# Arduino_LCD_Clock_rev_1.net
KiCad netlist of a schematic drawn in EAGLE
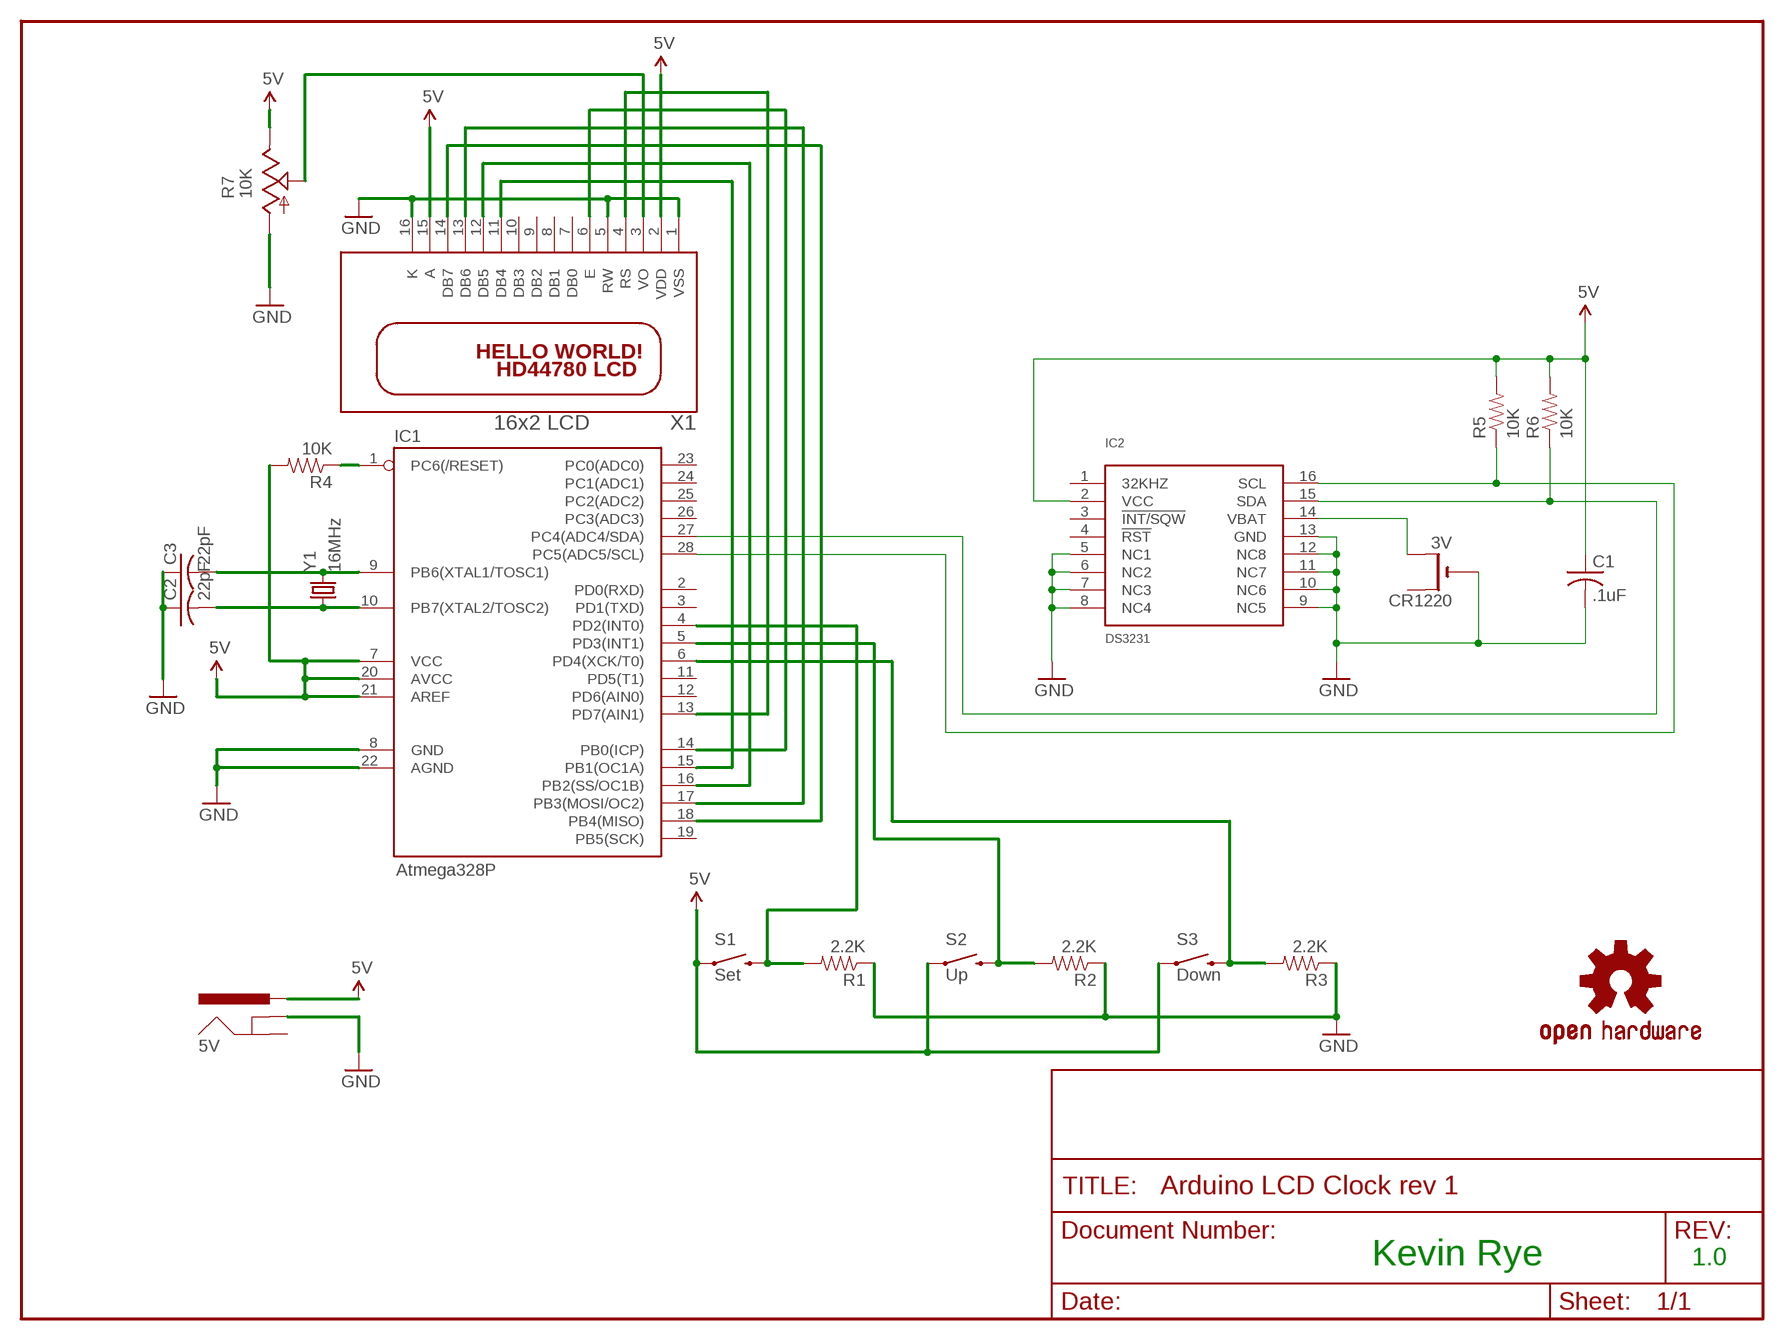
[diagram p0: schematic, sheet 1]

(export (version "E")
  (design (tool "Eeschema 10.0.6"))
  (components
    (comp (ref "5V")
      (value "POWER_JACKSLT")
      (footprint "eagle-import:POWER_JACK_SLOT")
      (libsource (lib "eagle-import") (part "POWER_JACKSLT"))
    )
    (comp (ref "C1")
      (value ".1uF")
      (footprint "eagle-import:C025-024X044")
      (libsource (lib "eagle-import") (part "C-US025-024X044"))
    )
    (comp (ref "C2")
      (value "22pF")
      (footprint "eagle-import:C025-024X044")
      (libsource (lib "eagle-import") (part "C-US025-024X044"))
    )
    (comp (ref "C3")
      (value "22pF")
      (footprint "eagle-import:C025-024X044")
      (libsource (lib "eagle-import") (part "C-US025-024X044"))
    )
    (comp (ref "CR1220")
      (value "3V")
      (footprint "eagle-import:CR1220-THM")
      (libsource (lib "eagle-import") (part "CR1220THM"))
    )
    (comp (ref "IC1")
      (value "Atmega328P")
      (footprint "eagle-import:DIL28-3")
      (libsource (lib "eagle-import") (part "AVR-MEGA8-PPTH"))
    )
    (comp (ref "IC2")
      (value "DS3231")
      (footprint "eagle-import:SO16W")
      (libsource (lib "eagle-import") (part "DS3231SN"))
    )
    (comp (ref "R1")
      (value "2.2K")
      (footprint "eagle-import:AXIAL-0.4")
      (libsource (lib "eagle-import") (part "RESISTORPTH-1/4W"))
    )
    (comp (ref "R2")
      (value "2.2K")
      (footprint "eagle-import:AXIAL-0.4")
      (libsource (lib "eagle-import") (part "RESISTORPTH-1/4W"))
    )
    (comp (ref "R3")
      (value "2.2K")
      (footprint "eagle-import:AXIAL-0.4")
      (libsource (lib "eagle-import") (part "RESISTORPTH-1/4W"))
    )
    (comp (ref "R4")
      (value "10K")
      (footprint "eagle-import:AXIAL-0.4")
      (libsource (lib "eagle-import") (part "RESISTORPTH-1/4W"))
    )
    (comp (ref "R5")
      (value "10K")
      (footprint "eagle-import:AXIAL-0.4")
      (libsource (lib "eagle-import") (part "RESISTORPTH-1/4W"))
    )
    (comp (ref "R6")
      (value "10K")
      (footprint "eagle-import:AXIAL-0.4")
      (libsource (lib "eagle-import") (part "RESISTORPTH-1/4W"))
    )
    (comp (ref "R7")
      (value "10K")
      (footprint "eagle-import:S63S")
      (libsource (lib "eagle-import") (part "TRIM_US-S63S"))
    )
    (comp (ref "S1")
      (value "Set")
      (footprint "eagle-import:TACTILE-PTH-12MM")
      (libsource (lib "eagle-import") (part "SWITCH-MOMENTARY-212MM"))
    )
    (comp (ref "S2")
      (value "Up")
      (footprint "eagle-import:TACTILE-PTH-12MM")
      (libsource (lib "eagle-import") (part "SWITCH-MOMENTARY-212MM"))
    )
    (comp (ref "S3")
      (value "Down")
      (footprint "eagle-import:TACTILE-PTH-12MM")
      (libsource (lib "eagle-import") (part "SWITCH-MOMENTARY-212MM"))
    )
    (comp (ref "U$2")
      (value "OSHW-LOGOM")
      (footprint "eagle-import:OSHW-LOGO-M")
      (libsource (lib "eagle-import") (part "OSHW-LOGOM"))
    )
    (comp (ref "X1")
      (value "16x2 LCD")
      (footprint "eagle-import:LCD1602")
      (libsource (lib "eagle-import") (part "HD44780LCD-1602"))
    )
    (comp (ref "Y1")
      (value "16MHz")
      (footprint "eagle-import:HC49US")
      (libsource (lib "eagle-import") (part "CRYSTALHC49US"))
    )
  )
  (nets
    (net (code "1") (name "5V") (class "Default")
      (node (ref "5V") (pin "PWR") (pinfunction "PWR_PWR") (pintype "bidirectional"))
      (node (ref "C1") (pin "1") (pinfunction "1_1") (pintype "passive"))
      (node (ref "IC1") (pin "20") (pinfunction "AVCC_20") (pintype "bidirectional"))
      (node (ref "IC1") (pin "21") (pinfunction "AREF_21") (pintype "bidirectional"))
      (node (ref "IC1") (pin "7") (pinfunction "VCC_7") (pintype "bidirectional"))
      (node (ref "IC2") (pin "2") (pinfunction "VCC_2") (pintype "bidirectional"))
      (node (ref "R4") (pin "P$2") (pinfunction "2_P$2") (pintype "passive"))
      (node (ref "R5") (pin "P$2") (pinfunction "2_P$2") (pintype "passive"))
      (node (ref "R6") (pin "P$2") (pinfunction "2_P$2") (pintype "passive"))
      (node (ref "R7") (pin "E") (pinfunction "E_E") (pintype "passive"))
      (node (ref "S1") (pin "1") (pinfunction "1_1") (pintype "passive"))
      (node (ref "S2") (pin "1") (pinfunction "1_1") (pintype "passive"))
      (node (ref "S3") (pin "1") (pinfunction "1_1") (pintype "passive"))
      (node (ref "X1") (pin "15") (pinfunction "A_15") (pintype "input"))
      (node (ref "X1") (pin "2") (pinfunction "VDD_2") (pintype "power_in"))
    )
    (net (code "2") (name "GND") (class "Default")
      (node (ref "5V") (pin "GND@1") (pinfunction "GNDBREAK_GND@1") (pintype "bidirectional"))
      (node (ref "C1") (pin "2") (pinfunction "2_2") (pintype "passive"))
      (node (ref "C2") (pin "1") (pinfunction "1_1") (pintype "passive"))
      (node (ref "C3") (pin "1") (pinfunction "1_1") (pintype "passive"))
      (node (ref "CR1220") (pin "-") (pinfunction "-_-") (pintype "passive"))
      (node (ref "IC1") (pin "22") (pinfunction "AGND_22") (pintype "bidirectional"))
      (node (ref "IC1") (pin "8") (pinfunction "GND_8") (pintype "bidirectional"))
      (node (ref "IC2") (pin "10") (pinfunction "NC6_10") (pintype "bidirectional"))
      (node (ref "IC2") (pin "11") (pinfunction "NC7_11") (pintype "bidirectional"))
      (node (ref "IC2") (pin "12") (pinfunction "NC8_12") (pintype "bidirectional"))
      (node (ref "IC2") (pin "13") (pinfunction "GND_13") (pintype "bidirectional"))
      (node (ref "IC2") (pin "5") (pinfunction "NC1_5") (pintype "bidirectional"))
      (node (ref "IC2") (pin "6") (pinfunction "NC2_6") (pintype "bidirectional"))
      (node (ref "IC2") (pin "7") (pinfunction "NC3_7") (pintype "bidirectional"))
      (node (ref "IC2") (pin "8") (pinfunction "NC4_8") (pintype "bidirectional"))
      (node (ref "IC2") (pin "9") (pinfunction "NC5_9") (pintype "bidirectional"))
      (node (ref "R1") (pin "P$1") (pinfunction "1_P$1") (pintype "passive"))
      (node (ref "R2") (pin "P$1") (pinfunction "1_P$1") (pintype "passive"))
      (node (ref "R3") (pin "P$1") (pinfunction "1_P$1") (pintype "passive"))
      (node (ref "R7") (pin "A") (pinfunction "A_A") (pintype "passive"))
      (node (ref "X1") (pin "1") (pinfunction "VSS_1") (pintype "power_in"))
      (node (ref "X1") (pin "16") (pinfunction "K_16") (pintype "input"))
      (node (ref "X1") (pin "5") (pinfunction "RW_5") (pintype "input"))
    )
    (net (code "3") (name "Net-(CR1220-+1)") (class "Default")
      (node (ref "CR1220") (pin "+2") (pinfunction "+1_+2") (pintype "passive"))
      (node (ref "IC2") (pin "14") (pinfunction "VBAT_14") (pintype "bidirectional"))
    )
    (net (code "4") (name "Net-(IC1-PB0(ICP))") (class "Default")
      (node (ref "IC1") (pin "14") (pinfunction "PB0(ICP)_14") (pintype "bidirectional"))
      (node (ref "X1") (pin "6") (pinfunction "E_6") (pintype "input"))
    )
    (net (code "5") (name "Net-(IC1-PB1(OC1A))") (class "Default")
      (node (ref "IC1") (pin "15") (pinfunction "PB1(OC1A)_15") (pintype "bidirectional"))
      (node (ref "X1") (pin "11") (pinfunction "DB4_11") (pintype "bidirectional"))
    )
    (net (code "6") (name "Net-(IC1-PB2(SS{slash}OC1B))") (class "Default")
      (node (ref "IC1") (pin "16") (pinfunction "PB2(SS/OC1B)_16") (pintype "bidirectional"))
      (node (ref "X1") (pin "12") (pinfunction "DB5_12") (pintype "bidirectional"))
    )
    (net (code "7") (name "Net-(IC1-PB3(MOSI{slash}OC2))") (class "Default")
      (node (ref "IC1") (pin "17") (pinfunction "PB3(MOSI/OC2)_17") (pintype "bidirectional"))
      (node (ref "X1") (pin "13") (pinfunction "DB6_13") (pintype "bidirectional"))
    )
    (net (code "8") (name "Net-(IC1-PB4(MISO))") (class "Default")
      (node (ref "IC1") (pin "18") (pinfunction "PB4(MISO)_18") (pintype "bidirectional"))
      (node (ref "X1") (pin "14") (pinfunction "DB7_14") (pintype "bidirectional"))
    )
    (net (code "9") (name "Net-(IC1-PB6(XTAL1{slash}TOSC1))") (class "Default")
      (node (ref "C3") (pin "2") (pinfunction "2_2") (pintype "passive"))
      (node (ref "IC1") (pin "9") (pinfunction "PB6(XTAL1/TOSC1)_9") (pintype "bidirectional"))
      (node (ref "Y1") (pin "2") (pinfunction "2_2") (pintype "passive"))
    )
    (net (code "10") (name "Net-(IC1-PB7(XTAL2{slash}TOSC2))") (class "Default")
      (node (ref "C2") (pin "2") (pinfunction "2_2") (pintype "passive"))
      (node (ref "IC1") (pin "10") (pinfunction "PB7(XTAL2/TOSC2)_10") (pintype "bidirectional"))
      (node (ref "Y1") (pin "1") (pinfunction "1_1") (pintype "passive"))
    )
    (net (code "11") (name "Net-(IC1-PC4(ADC4{slash}SDA))") (class "Default")
      (node (ref "IC1") (pin "27") (pinfunction "PC4(ADC4/SDA)_27") (pintype "bidirectional"))
      (node (ref "IC2") (pin "15") (pinfunction "SDA_15") (pintype "bidirectional"))
      (node (ref "R6") (pin "P$1") (pinfunction "1_P$1") (pintype "passive"))
    )
    (net (code "12") (name "Net-(IC1-PC5(ADC5{slash}SCL))") (class "Default")
      (node (ref "IC1") (pin "28") (pinfunction "PC5(ADC5/SCL)_28") (pintype "bidirectional"))
      (node (ref "IC2") (pin "16") (pinfunction "SCL_16") (pintype "bidirectional"))
      (node (ref "R5") (pin "P$1") (pinfunction "1_P$1") (pintype "passive"))
    )
    (net (code "13") (name "Net-(IC1-PC6({slash}RESET))") (class "Default")
      (node (ref "IC1") (pin "1") (pinfunction "PC6(/RESET)_1") (pintype "bidirectional"))
      (node (ref "R4") (pin "P$1") (pinfunction "1_P$1") (pintype "passive"))
    )
    (net (code "14") (name "Net-(IC1-PD2(INT0))") (class "Default")
      (node (ref "IC1") (pin "4") (pinfunction "PD2(INT0)_4") (pintype "bidirectional"))
      (node (ref "R1") (pin "P$2") (pinfunction "2_P$2") (pintype "passive"))
      (node (ref "S1") (pin "3") (pinfunction "2_3") (pintype "passive"))
    )
    (net (code "15") (name "Net-(IC1-PD3(INT1))") (class "Default")
      (node (ref "IC1") (pin "5") (pinfunction "PD3(INT1)_5") (pintype "bidirectional"))
      (node (ref "R2") (pin "P$2") (pinfunction "2_P$2") (pintype "passive"))
      (node (ref "S2") (pin "3") (pinfunction "2_3") (pintype "passive"))
    )
    (net (code "16") (name "Net-(IC1-PD4(XCK{slash}T0))") (class "Default")
      (node (ref "IC1") (pin "6") (pinfunction "PD4(XCK/T0)_6") (pintype "bidirectional"))
      (node (ref "R3") (pin "P$2") (pinfunction "2_P$2") (pintype "passive"))
      (node (ref "S3") (pin "3") (pinfunction "2_3") (pintype "passive"))
    )
    (net (code "17") (name "Net-(IC1-PD7(AIN1))") (class "Default")
      (node (ref "IC1") (pin "13") (pinfunction "PD7(AIN1)_13") (pintype "bidirectional"))
      (node (ref "X1") (pin "4") (pinfunction "RS_4") (pintype "input"))
    )
    (net (code "18") (name "Net-(X1-VO)") (class "Default")
      (node (ref "R7") (pin "S") (pinfunction "S_S") (pintype "passive"))
      (node (ref "X1") (pin "3") (pinfunction "VO_3") (pintype "input"))
    )
    (net (code "19") (name "unconnected-(5V-GND-PadGND@2)") (class "Default")
      (node (ref "5V") (pin "GND@2") (pinfunction "GND_GND@2") (pintype "bidirectional"))
    )
    (net (code "20") (name "unconnected-(CR1220-+-Pad+1)") (class "Default")
      (node (ref "CR1220") (pin "+1") (pinfunction "+_+1") (pintype "passive"))
    )
    (net (code "21") (name "unconnected-(IC1-PB5(SCK)-Pad19)") (class "Default")
      (node (ref "IC1") (pin "19") (pinfunction "PB5(SCK)_19") (pintype "bidirectional"))
    )
    (net (code "22") (name "unconnected-(IC1-PC0(ADC0)-Pad23)") (class "Default")
      (node (ref "IC1") (pin "23") (pinfunction "PC0(ADC0)_23") (pintype "bidirectional"))
    )
    (net (code "23") (name "unconnected-(IC1-PC1(ADC1)-Pad24)") (class "Default")
      (node (ref "IC1") (pin "24") (pinfunction "PC1(ADC1)_24") (pintype "bidirectional"))
    )
    (net (code "24") (name "unconnected-(IC1-PC2(ADC2)-Pad25)") (class "Default")
      (node (ref "IC1") (pin "25") (pinfunction "PC2(ADC2)_25") (pintype "bidirectional"))
    )
    (net (code "25") (name "unconnected-(IC1-PC3(ADC3)-Pad26)") (class "Default")
      (node (ref "IC1") (pin "26") (pinfunction "PC3(ADC3)_26") (pintype "bidirectional"))
    )
    (net (code "26") (name "unconnected-(IC1-PD0(RXD)-Pad2)") (class "Default")
      (node (ref "IC1") (pin "2") (pinfunction "PD0(RXD)_2") (pintype "bidirectional"))
    )
    (net (code "27") (name "unconnected-(IC1-PD1(TXD)-Pad3)") (class "Default")
      (node (ref "IC1") (pin "3") (pinfunction "PD1(TXD)_3") (pintype "bidirectional"))
    )
    (net (code "28") (name "unconnected-(IC1-PD5(T1)-Pad11)") (class "Default")
      (node (ref "IC1") (pin "11") (pinfunction "PD5(T1)_11") (pintype "bidirectional"))
    )
    (net (code "29") (name "unconnected-(IC1-PD6(AIN0)-Pad12)") (class "Default")
      (node (ref "IC1") (pin "12") (pinfunction "PD6(AIN0)_12") (pintype "bidirectional"))
    )
    (net (code "30") (name "unconnected-(IC2-32KHZ-Pad1)") (class "Default")
      (node (ref "IC2") (pin "1") (pinfunction "32KHZ_1") (pintype "bidirectional"))
    )
    (net (code "31") (name "unconnected-(IC2-~{INT{slash}SQW}-Pad3)") (class "Default")
      (node (ref "IC2") (pin "3") (pinfunction "~{INT/SQW}_3") (pintype "bidirectional"))
    )
    (net (code "32") (name "unconnected-(IC2-~{RST}-Pad4)") (class "Default")
      (node (ref "IC2") (pin "4") (pinfunction "~{RST}_4") (pintype "bidirectional"))
    )
    (net (code "33") (name "unconnected-(X1-DB0-Pad7)") (class "Default")
      (node (ref "X1") (pin "7") (pinfunction "DB0_7") (pintype "bidirectional"))
    )
    (net (code "34") (name "unconnected-(X1-DB1-Pad8)") (class "Default")
      (node (ref "X1") (pin "8") (pinfunction "DB1_8") (pintype "bidirectional"))
    )
    (net (code "35") (name "unconnected-(X1-DB2-Pad9)") (class "Default")
      (node (ref "X1") (pin "9") (pinfunction "DB2_9") (pintype "bidirectional"))
    )
    (net (code "36") (name "unconnected-(X1-DB3-Pad10)") (class "Default")
      (node (ref "X1") (pin "10") (pinfunction "DB3_10") (pintype "bidirectional"))
    )
  )
)
